# MOSFETs.net
KiCad netlist of a schematic drawn in Altium Designer
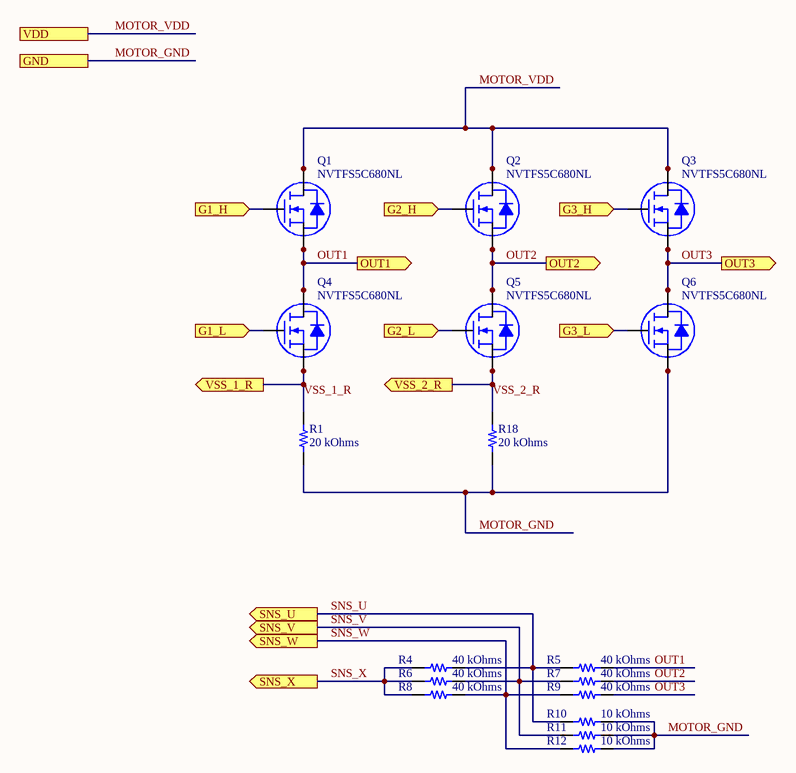
[diagram p0: MOSFETs.SchDoc]

(export (version "E")
  (design (tool "Eeschema 10.0.6"))
  (components
    (comp (ref "Q1")
      (value "NVTFS5C680NL")
      (footprint "NVTFS015N04CTAG")
      (description "N-FET")
      (libsource (lib "IC") (part "NVTFS5C680NL"))
    )
    (comp (ref "Q2")
      (value "NVTFS5C680NL")
      (footprint "NVTFS015N04CTAG")
      (description "N-FET")
      (libsource (lib "IC") (part "NVTFS5C680NL"))
    )
    (comp (ref "Q3")
      (value "NVTFS5C680NL")
      (footprint "NVTFS015N04CTAG")
      (description "N-FET")
      (libsource (lib "IC") (part "NVTFS5C680NL"))
    )
    (comp (ref "Q4")
      (value "NVTFS5C680NL")
      (footprint "NVTFS015N04CTAG")
      (description "N-FET")
      (libsource (lib "IC") (part "NVTFS5C680NL"))
    )
    (comp (ref "Q5")
      (value "NVTFS5C680NL")
      (footprint "NVTFS015N04CTAG")
      (description "N-FET")
      (libsource (lib "IC") (part "NVTFS5C680NL"))
    )
    (comp (ref "Q6")
      (value "NVTFS5C680NL")
      (footprint "NVTFS015N04CTAG")
      (description "N-FET")
      (libsource (lib "IC") (part "NVTFS5C680NL"))
    )
    (comp (ref "R1")
      (value "20 kOhms")
      (footprint "RES 0805_2012")
      (description "RES SMD 20K OHM 0.1% 1W 0805")
      (fields
        (field (name "PART NUMBER") "PCAN0805E2002BST5")
        (field (name "MANUFACTURER") "Vishay Thin Film")
      )
      (libsource (lib "Celestial Altium Library - altium_library") (part "Resistor"))
    )
    (comp (ref "R4")
      (value "40 kOhms")
      (footprint "RES 0402_1005")
      (description "RES 14.3K OHM 1% 1/10W 0402")
      (fields
        (field (name "PART NUMBER") "RK73H1ETTP1432F")
        (field (name "MANUFACTURER") "KOA Speer Electronics, Inc.")
      )
      (libsource (lib "Celestial Altium Library - altium_library") (part "Resistor"))
    )
    (comp (ref "R5")
      (value "40 kOhms")
      (footprint "RES 0402_1005")
      (description "RES 14.3K OHM 1% 1/10W 0402")
      (fields
        (field (name "PART NUMBER") "RK73H1ETTP1432F")
        (field (name "MANUFACTURER") "KOA Speer Electronics, Inc.")
      )
      (libsource (lib "Celestial Altium Library - altium_library") (part "Resistor"))
    )
    (comp (ref "R6")
      (value "40 kOhms")
      (footprint "RES 0402_1005")
      (description "RES 14.3K OHM 1% 1/10W 0402")
      (fields
        (field (name "PART NUMBER") "RK73H1ETTP1432F")
        (field (name "MANUFACTURER") "KOA Speer Electronics, Inc.")
      )
      (libsource (lib "Celestial Altium Library - altium_library") (part "Resistor"))
    )
    (comp (ref "R7")
      (value "40 kOhms")
      (footprint "RES 0402_1005")
      (description "RES 14.3K OHM 1% 1/10W 0402")
      (fields
        (field (name "PART NUMBER") "RK73H1ETTP1432F")
        (field (name "MANUFACTURER") "KOA Speer Electronics, Inc.")
      )
      (libsource (lib "Celestial Altium Library - altium_library") (part "Resistor"))
    )
    (comp (ref "R8")
      (value "40 kOhms")
      (footprint "RES 0402_1005")
      (description "RES 14.3K OHM 1% 1/10W 0402")
      (fields
        (field (name "PART NUMBER") "RK73H1ETTP1432F")
        (field (name "MANUFACTURER") "KOA Speer Electronics, Inc.")
      )
      (libsource (lib "Celestial Altium Library - altium_library") (part "Resistor"))
    )
    (comp (ref "R9")
      (value "40 kOhms")
      (footprint "RES 0402_1005")
      (description "RES 14.3K OHM 1% 1/10W 0402")
      (fields
        (field (name "PART NUMBER") "RK73H1ETTP1432F")
        (field (name "MANUFACTURER") "KOA Speer Electronics, Inc.")
      )
      (libsource (lib "Celestial Altium Library - altium_library") (part "Resistor"))
    )
    (comp (ref "R10")
      (value "10 kOhms")
      (footprint "RES 0402_1005")
      (description "RES 14.3K OHM 1% 1/10W 0402")
      (fields
        (field (name "PART NUMBER") "RK73H1ETTP1432F")
        (field (name "MANUFACTURER") "KOA Speer Electronics, Inc.")
      )
      (libsource (lib "Celestial Altium Library - altium_library") (part "Resistor"))
    )
    (comp (ref "R11")
      (value "10 kOhms")
      (footprint "RES 0402_1005")
      (description "RES 14.3K OHM 1% 1/10W 0402")
      (fields
        (field (name "PART NUMBER") "RK73H1ETTP1432F")
        (field (name "MANUFACTURER") "KOA Speer Electronics, Inc.")
      )
      (libsource (lib "Celestial Altium Library - altium_library") (part "Resistor"))
    )
    (comp (ref "R12")
      (value "10 kOhms")
      (footprint "RES 0402_1005")
      (description "RES 14.3K OHM 1% 1/10W 0402")
      (fields
        (field (name "PART NUMBER") "RK73H1ETTP1432F")
        (field (name "MANUFACTURER") "KOA Speer Electronics, Inc.")
      )
      (libsource (lib "Celestial Altium Library - altium_library") (part "Resistor"))
    )
    (comp (ref "R18")
      (value "20 kOhms")
      (footprint "RES 0805_2012")
      (description "RES SMD 20K OHM 0.1% 1W 0805")
      (fields
        (field (name "PART NUMBER") "PCAN0805E2002BST5")
        (field (name "MANUFACTURER") "Vishay Thin Film")
      )
      (libsource (lib "Celestial Altium Library - altium_library") (part "Resistor"))
    )
  )
  (nets
    (net (code "1") (name "/G1_H") (class "Default")
      (node (ref "Q1") (pin "4") (pinfunction "G_4") (pintype "passive"))
    )
    (net (code "2") (name "/G1_L") (class "Default")
      (node (ref "Q4") (pin "4") (pinfunction "G_4") (pintype "passive"))
    )
    (net (code "3") (name "/G2_H") (class "Default")
      (node (ref "Q2") (pin "4") (pinfunction "G_4") (pintype "passive"))
    )
    (net (code "4") (name "/G2_L") (class "Default")
      (node (ref "Q5") (pin "4") (pinfunction "G_4") (pintype "passive"))
    )
    (net (code "5") (name "/G3_H") (class "Default")
      (node (ref "Q3") (pin "4") (pinfunction "G_4") (pintype "passive"))
    )
    (net (code "6") (name "/G3_L") (class "Default")
      (node (ref "Q6") (pin "4") (pinfunction "G_4") (pintype "passive"))
    )
    (net (code "7") (name "/MOTOR_GND") (class "Default")
      (node (ref "Q6") (pin "1") (pinfunction "S_1") (pintype "passive"))
      (node (ref "Q6") (pin "2") (pinfunction "S_2") (pintype "passive"))
      (node (ref "Q6") (pin "3") (pinfunction "S_3") (pintype "passive"))
      (node (ref "R1") (pin "1") (pinfunction "1_1") (pintype "passive"))
      (node (ref "R10") (pin "1") (pinfunction "1_1") (pintype "passive"))
      (node (ref "R11") (pin "1") (pinfunction "1_1") (pintype "passive"))
      (node (ref "R12") (pin "1") (pinfunction "1_1") (pintype "passive"))
      (node (ref "R18") (pin "1") (pinfunction "1_1") (pintype "passive"))
    )
    (net (code "8") (name "/MOTOR_VDD") (class "Default")
      (node (ref "Q1") (pin "5") (pinfunction "D_5") (pintype "passive"))
      (node (ref "Q1") (pin "6") (pinfunction "D_6") (pintype "passive"))
      (node (ref "Q1") (pin "7") (pinfunction "D_7") (pintype "passive"))
      (node (ref "Q1") (pin "8") (pinfunction "D_8") (pintype "passive"))
      (node (ref "Q2") (pin "5") (pinfunction "D_5") (pintype "passive"))
      (node (ref "Q2") (pin "6") (pinfunction "D_6") (pintype "passive"))
      (node (ref "Q2") (pin "7") (pinfunction "D_7") (pintype "passive"))
      (node (ref "Q2") (pin "8") (pinfunction "D_8") (pintype "passive"))
      (node (ref "Q3") (pin "5") (pinfunction "D_5") (pintype "passive"))
      (node (ref "Q3") (pin "6") (pinfunction "D_6") (pintype "passive"))
      (node (ref "Q3") (pin "7") (pinfunction "D_7") (pintype "passive"))
      (node (ref "Q3") (pin "8") (pinfunction "D_8") (pintype "passive"))
    )
    (net (code "9") (name "/OUT1") (class "Default")
      (node (ref "Q1") (pin "1") (pinfunction "S_1") (pintype "passive"))
      (node (ref "Q1") (pin "2") (pinfunction "S_2") (pintype "passive"))
      (node (ref "Q1") (pin "3") (pinfunction "S_3") (pintype "passive"))
      (node (ref "Q4") (pin "5") (pinfunction "D_5") (pintype "passive"))
      (node (ref "Q4") (pin "6") (pinfunction "D_6") (pintype "passive"))
      (node (ref "Q4") (pin "7") (pinfunction "D_7") (pintype "passive"))
      (node (ref "Q4") (pin "8") (pinfunction "D_8") (pintype "passive"))
      (node (ref "R5") (pin "2") (pinfunction "2_2") (pintype "passive"))
    )
    (net (code "10") (name "/OUT2") (class "Default")
      (node (ref "Q2") (pin "1") (pinfunction "S_1") (pintype "passive"))
      (node (ref "Q2") (pin "2") (pinfunction "S_2") (pintype "passive"))
      (node (ref "Q2") (pin "3") (pinfunction "S_3") (pintype "passive"))
      (node (ref "Q5") (pin "5") (pinfunction "D_5") (pintype "passive"))
      (node (ref "Q5") (pin "6") (pinfunction "D_6") (pintype "passive"))
      (node (ref "Q5") (pin "7") (pinfunction "D_7") (pintype "passive"))
      (node (ref "Q5") (pin "8") (pinfunction "D_8") (pintype "passive"))
      (node (ref "R7") (pin "2") (pinfunction "2_2") (pintype "passive"))
    )
    (net (code "11") (name "/OUT3") (class "Default")
      (node (ref "Q3") (pin "1") (pinfunction "S_1") (pintype "passive"))
      (node (ref "Q3") (pin "2") (pinfunction "S_2") (pintype "passive"))
      (node (ref "Q3") (pin "3") (pinfunction "S_3") (pintype "passive"))
      (node (ref "Q6") (pin "5") (pinfunction "D_5") (pintype "passive"))
      (node (ref "Q6") (pin "6") (pinfunction "D_6") (pintype "passive"))
      (node (ref "Q6") (pin "7") (pinfunction "D_7") (pintype "passive"))
      (node (ref "Q6") (pin "8") (pinfunction "D_8") (pintype "passive"))
      (node (ref "R9") (pin "2") (pinfunction "2_2") (pintype "passive"))
    )
    (net (code "12") (name "/SNS_U") (class "Default")
      (node (ref "R10") (pin "2") (pinfunction "2_2") (pintype "passive"))
      (node (ref "R4") (pin "2") (pinfunction "2_2") (pintype "passive"))
      (node (ref "R5") (pin "1") (pinfunction "1_1") (pintype "passive"))
    )
    (net (code "13") (name "/SNS_V") (class "Default")
      (node (ref "R11") (pin "2") (pinfunction "2_2") (pintype "passive"))
      (node (ref "R6") (pin "2") (pinfunction "2_2") (pintype "passive"))
      (node (ref "R7") (pin "1") (pinfunction "1_1") (pintype "passive"))
    )
    (net (code "14") (name "/SNS_W") (class "Default")
      (node (ref "R12") (pin "2") (pinfunction "2_2") (pintype "passive"))
      (node (ref "R8") (pin "2") (pinfunction "2_2") (pintype "passive"))
      (node (ref "R9") (pin "1") (pinfunction "1_1") (pintype "passive"))
    )
    (net (code "15") (name "/SNS_X") (class "Default")
      (node (ref "R4") (pin "1") (pinfunction "1_1") (pintype "passive"))
      (node (ref "R6") (pin "1") (pinfunction "1_1") (pintype "passive"))
      (node (ref "R8") (pin "1") (pinfunction "1_1") (pintype "passive"))
    )
    (net (code "16") (name "/VSS_1_R") (class "Default")
      (node (ref "Q4") (pin "1") (pinfunction "S_1") (pintype "passive"))
      (node (ref "Q4") (pin "2") (pinfunction "S_2") (pintype "passive"))
      (node (ref "Q4") (pin "3") (pinfunction "S_3") (pintype "passive"))
      (node (ref "R1") (pin "2") (pinfunction "2_2") (pintype "passive"))
    )
    (net (code "17") (name "/VSS_2_R") (class "Default")
      (node (ref "Q5") (pin "1") (pinfunction "S_1") (pintype "passive"))
      (node (ref "Q5") (pin "2") (pinfunction "S_2") (pintype "passive"))
      (node (ref "Q5") (pin "3") (pinfunction "S_3") (pintype "passive"))
      (node (ref "R18") (pin "2") (pinfunction "2_2") (pintype "passive"))
    )
  )
)
